# untitled.net
KiCad netlist of a schematic drawn in EAGLE
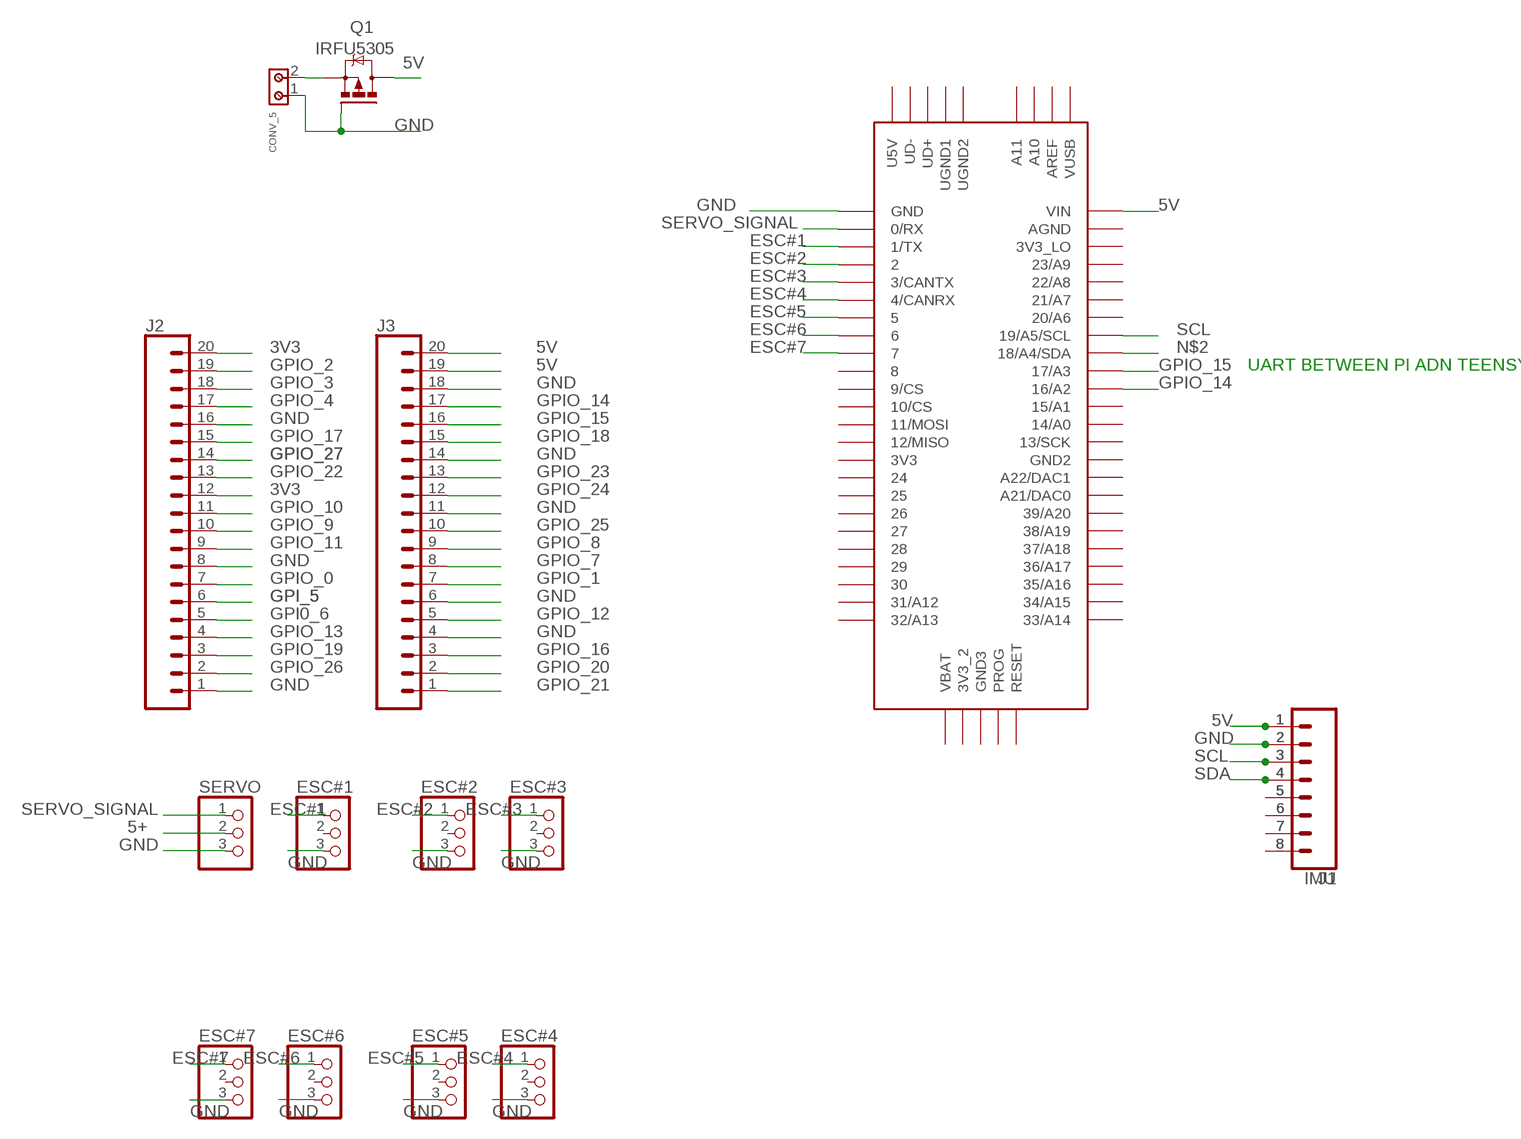
[diagram p0: schematic, sheet 1]

(export (version "E")
  (design (tool "Eeschema 10.0.6"))
  (components
    (comp (ref "CONV_5")
      (value "691213500002")
      (footprint "eagle-import:691213500002")
      (libsource (lib "eagle-import") (part "691213500002"))
    )
    (comp (ref "ESC#1")
      (value "PINHD-1X3")
      (footprint "eagle-import:1X03")
      (libsource (lib "eagle-import") (part "PINHD-1X3"))
    )
    (comp (ref "ESC#2")
      (value "PINHD-1X3")
      (footprint "eagle-import:1X03")
      (libsource (lib "eagle-import") (part "PINHD-1X3"))
    )
    (comp (ref "ESC#3")
      (value "PINHD-1X3")
      (footprint "eagle-import:1X03")
      (libsource (lib "eagle-import") (part "PINHD-1X3"))
    )
    (comp (ref "ESC#4")
      (value "PINHD-1X3")
      (footprint "eagle-import:1X03")
      (libsource (lib "eagle-import") (part "PINHD-1X3"))
    )
    (comp (ref "ESC#5")
      (value "PINHD-1X3")
      (footprint "eagle-import:1X03")
      (libsource (lib "eagle-import") (part "PINHD-1X3"))
    )
    (comp (ref "ESC#6")
      (value "PINHD-1X3")
      (footprint "eagle-import:1X03")
      (libsource (lib "eagle-import") (part "PINHD-1X3"))
    )
    (comp (ref "ESC#7")
      (value "PINHD-1X3")
      (footprint "eagle-import:1X03")
      (libsource (lib "eagle-import") (part "PINHD-1X3"))
    )
    (comp (ref "IMU")
      (value "CONN_08\"")
      (footprint "eagle-import:1X08")
      (libsource (lib "eagle-import") (part "CONN_08{dblquote}"))
    )
    (comp (ref "J1")
      (value "CONN_08\"")
      (footprint "eagle-import:1X08")
      (libsource (lib "eagle-import") (part "CONN_08{dblquote}"))
    )
    (comp (ref "J2")
      (value "CONN_20")
      (footprint "eagle-import:1X20")
      (libsource (lib "eagle-import") (part "CONN_20"))
    )
    (comp (ref "J3")
      (value "CONN_20")
      (footprint "eagle-import:1X20")
      (libsource (lib "eagle-import") (part "CONN_20"))
    )
    (comp (ref "Q1")
      (value "IRFU5305")
      (footprint "eagle-import:I-PAK_TO251AA")
      (libsource (lib "eagle-import") (part "IRF?5305U"))
    )
    (comp (ref "SERVO")
      (value "PINHD-1X3")
      (footprint "eagle-import:1X03")
      (libsource (lib "eagle-import") (part "PINHD-1X3"))
    )
    (comp (ref "U$1")
      (value "TEENSY_3.5/3.6")
      (footprint "eagle-import:TEENSY_3.5_3.6")
      (libsource (lib "eagle-import") (part "TEENSY_3.5/3.6"))
    )
  )
  (nets
    (net (code "1") (name "/3V3") (class "Default")
      (node (ref "J2") (pin "12") (pinfunction "12_12") (pintype "passive"))
      (node (ref "J2") (pin "20") (pinfunction "20_20") (pintype "passive"))
    )
    (net (code "2") (name "/5+") (class "Default")
      (node (ref "SERVO") (pin "2") (pinfunction "2_2") (pintype "passive"))
    )
    (net (code "3") (name "/5V") (class "Default")
      (node (ref "IMU") (pin "1") (pinfunction "1_1") (pintype "passive"))
      (node (ref "J1") (pin "1") (pinfunction "1_1") (pintype "passive"))
      (node (ref "J3") (pin "19") (pinfunction "19_19") (pintype "passive"))
      (node (ref "J3") (pin "20") (pinfunction "20_20") (pintype "passive"))
      (node (ref "Q1") (pin "2") (pinfunction "D_2") (pintype "passive"))
      (node (ref "U$1") (pin "VIN") (pinfunction "VIN_VIN") (pintype "bidirectional"))
    )
    (net (code "4") (name "/ESC#1") (class "Default")
      (node (ref "ESC#1") (pin "1") (pinfunction "1_1") (pintype "passive"))
      (node (ref "U$1") (pin "1/TX") (pinfunction "1/TX_1/TX") (pintype "bidirectional"))
    )
    (net (code "5") (name "/ESC#2") (class "Default")
      (node (ref "ESC#2") (pin "1") (pinfunction "1_1") (pintype "passive"))
      (node (ref "U$1") (pin "2") (pinfunction "2_2") (pintype "bidirectional"))
    )
    (net (code "6") (name "/ESC#3") (class "Default")
      (node (ref "ESC#3") (pin "1") (pinfunction "1_1") (pintype "passive"))
      (node (ref "U$1") (pin "3/CANTX") (pinfunction "3/CANTX_3/CANTX") (pintype "bidirectional"))
    )
    (net (code "7") (name "/ESC#4") (class "Default")
      (node (ref "ESC#4") (pin "1") (pinfunction "1_1") (pintype "passive"))
      (node (ref "U$1") (pin "4/CANRX") (pinfunction "4/CANRX_4/CANRX") (pintype "bidirectional"))
    )
    (net (code "8") (name "/ESC#5") (class "Default")
      (node (ref "ESC#5") (pin "1") (pinfunction "1_1") (pintype "passive"))
      (node (ref "U$1") (pin "5") (pinfunction "5_5") (pintype "bidirectional"))
    )
    (net (code "9") (name "/ESC#6") (class "Default")
      (node (ref "ESC#6") (pin "1") (pinfunction "1_1") (pintype "passive"))
      (node (ref "U$1") (pin "6") (pinfunction "6_6") (pintype "bidirectional"))
    )
    (net (code "10") (name "/ESC#7") (class "Default")
      (node (ref "ESC#7") (pin "1") (pinfunction "1_1") (pintype "passive"))
      (node (ref "U$1") (pin "7") (pinfunction "7_7") (pintype "bidirectional"))
    )
    (net (code "11") (name "/GND") (class "Default")
      (node (ref "CONV_5") (pin "1") (pinfunction "1_1") (pintype "passive"))
      (node (ref "ESC#1") (pin "3") (pinfunction "3_3") (pintype "passive"))
      (node (ref "ESC#2") (pin "3") (pinfunction "3_3") (pintype "passive"))
      (node (ref "ESC#3") (pin "3") (pinfunction "3_3") (pintype "passive"))
      (node (ref "ESC#4") (pin "3") (pinfunction "3_3") (pintype "passive"))
      (node (ref "ESC#5") (pin "3") (pinfunction "3_3") (pintype "passive"))
      (node (ref "ESC#6") (pin "3") (pinfunction "3_3") (pintype "passive"))
      (node (ref "ESC#7") (pin "3") (pinfunction "3_3") (pintype "passive"))
      (node (ref "IMU") (pin "2") (pinfunction "2_2") (pintype "passive"))
      (node (ref "J1") (pin "2") (pinfunction "2_2") (pintype "passive"))
      (node (ref "J2") (pin "1") (pinfunction "1_1") (pintype "passive"))
      (node (ref "J2") (pin "16") (pinfunction "16_16") (pintype "passive"))
      (node (ref "J2") (pin "8") (pinfunction "8_8") (pintype "passive"))
      (node (ref "J3") (pin "11") (pinfunction "11_11") (pintype "passive"))
      (node (ref "J3") (pin "14") (pinfunction "14_14") (pintype "passive"))
      (node (ref "J3") (pin "18") (pinfunction "18_18") (pintype "passive"))
      (node (ref "J3") (pin "4") (pinfunction "4_4") (pintype "passive"))
      (node (ref "J3") (pin "6") (pinfunction "6_6") (pintype "passive"))
      (node (ref "Q1") (pin "1") (pinfunction "G_1") (pintype "passive"))
      (node (ref "SERVO") (pin "3") (pinfunction "3_3") (pintype "passive"))
      (node (ref "U$1") (pin "GND") (pinfunction "GND_GND") (pintype "bidirectional"))
    )
    (net (code "12") (name "/GPI0_6") (class "Default")
      (node (ref "J2") (pin "5") (pinfunction "5_5") (pintype "passive"))
    )
    (net (code "13") (name "/GPIO_0") (class "Default")
      (node (ref "J2") (pin "7") (pinfunction "7_7") (pintype "passive"))
    )
    (net (code "14") (name "/GPIO_1") (class "Default")
      (node (ref "J3") (pin "7") (pinfunction "7_7") (pintype "passive"))
    )
    (net (code "15") (name "/GPIO_2") (class "Default")
      (node (ref "J2") (pin "19") (pinfunction "19_19") (pintype "passive"))
    )
    (net (code "16") (name "/GPIO_3") (class "Default")
      (node (ref "J2") (pin "18") (pinfunction "18_18") (pintype "passive"))
    )
    (net (code "17") (name "/GPIO_4") (class "Default")
      (node (ref "J2") (pin "17") (pinfunction "17_17") (pintype "passive"))
    )
    (net (code "18") (name "/GPIO_7") (class "Default")
      (node (ref "J3") (pin "8") (pinfunction "8_8") (pintype "passive"))
    )
    (net (code "19") (name "/GPIO_8") (class "Default")
      (node (ref "J3") (pin "9") (pinfunction "9_9") (pintype "passive"))
    )
    (net (code "20") (name "/GPIO_9") (class "Default")
      (node (ref "J2") (pin "10") (pinfunction "10_10") (pintype "passive"))
    )
    (net (code "21") (name "/GPIO_10") (class "Default")
      (node (ref "J2") (pin "11") (pinfunction "11_11") (pintype "passive"))
    )
    (net (code "22") (name "/GPIO_11") (class "Default")
      (node (ref "J2") (pin "9") (pinfunction "9_9") (pintype "passive"))
    )
    (net (code "23") (name "/GPIO_12") (class "Default")
      (node (ref "J3") (pin "5") (pinfunction "5_5") (pintype "passive"))
    )
    (net (code "24") (name "/GPIO_13") (class "Default")
      (node (ref "J2") (pin "4") (pinfunction "4_4") (pintype "passive"))
    )
    (net (code "25") (name "/GPIO_14") (class "Default")
      (node (ref "J3") (pin "17") (pinfunction "17_17") (pintype "passive"))
      (node (ref "U$1") (pin "16/A2") (pinfunction "16/A2_16/A2") (pintype "bidirectional"))
    )
    (net (code "26") (name "/GPIO_15") (class "Default")
      (node (ref "J3") (pin "16") (pinfunction "16_16") (pintype "passive"))
      (node (ref "U$1") (pin "17/A3") (pinfunction "17/A3_17/A3") (pintype "bidirectional"))
    )
    (net (code "27") (name "/GPIO_16") (class "Default")
      (node (ref "J3") (pin "3") (pinfunction "3_3") (pintype "passive"))
    )
    (net (code "28") (name "/GPIO_17") (class "Default")
      (node (ref "J2") (pin "15") (pinfunction "15_15") (pintype "passive"))
    )
    (net (code "29") (name "/GPIO_18") (class "Default")
      (node (ref "J3") (pin "15") (pinfunction "15_15") (pintype "passive"))
    )
    (net (code "30") (name "/GPIO_19") (class "Default")
      (node (ref "J2") (pin "3") (pinfunction "3_3") (pintype "passive"))
    )
    (net (code "31") (name "/GPIO_20") (class "Default")
      (node (ref "J3") (pin "2") (pinfunction "2_2") (pintype "passive"))
    )
    (net (code "32") (name "/GPIO_21") (class "Default")
      (node (ref "J3") (pin "1") (pinfunction "1_1") (pintype "passive"))
    )
    (net (code "33") (name "/GPIO_22") (class "Default")
      (node (ref "J2") (pin "13") (pinfunction "13_13") (pintype "passive"))
    )
    (net (code "34") (name "/GPIO_23") (class "Default")
      (node (ref "J3") (pin "13") (pinfunction "13_13") (pintype "passive"))
    )
    (net (code "35") (name "/GPIO_24") (class "Default")
      (node (ref "J3") (pin "12") (pinfunction "12_12") (pintype "passive"))
    )
    (net (code "36") (name "/GPIO_25") (class "Default")
      (node (ref "J3") (pin "10") (pinfunction "10_10") (pintype "passive"))
    )
    (net (code "37") (name "/GPIO_26") (class "Default")
      (node (ref "J2") (pin "2") (pinfunction "2_2") (pintype "passive"))
    )
    (net (code "38") (name "/GPIO_27") (class "Default")
      (node (ref "J2") (pin "14") (pinfunction "14_14") (pintype "passive"))
    )
    (net (code "39") (name "/GPI_5") (class "Default")
      (node (ref "J2") (pin "6") (pinfunction "6_6") (pintype "passive"))
    )
    (net (code "40") (name "/N$2") (class "Default")
      (node (ref "U$1") (pin "18/A4/SDA") (pinfunction "18/A4/SDA_18/A4/SDA") (pintype "bidirectional"))
    )
    (net (code "41") (name "/SCL") (class "Default")
      (node (ref "IMU") (pin "3") (pinfunction "3_3") (pintype "passive"))
      (node (ref "J1") (pin "3") (pinfunction "3_3") (pintype "passive"))
      (node (ref "U$1") (pin "19/A5/SCL") (pinfunction "19/A5/SCL_19/A5/SCL") (pintype "bidirectional"))
    )
    (net (code "42") (name "/SDA") (class "Default")
      (node (ref "IMU") (pin "4") (pinfunction "4_4") (pintype "passive"))
      (node (ref "J1") (pin "4") (pinfunction "4_4") (pintype "passive"))
    )
    (net (code "43") (name "/SERVO_SIGNAL") (class "Default")
      (node (ref "SERVO") (pin "1") (pinfunction "1_1") (pintype "passive"))
      (node (ref "U$1") (pin "0/RX") (pinfunction "0/RX_0/RX") (pintype "bidirectional"))
    )
    (net (code "44") (name "Net-(IMU-Pad5)") (class "Default")
      (node (ref "IMU") (pin "5") (pinfunction "5_5") (pintype "passive"))
      (node (ref "J1") (pin "5") (pinfunction "5_5") (pintype "passive"))
    )
    (net (code "45") (name "Net-(IMU-Pad6)") (class "Default")
      (node (ref "IMU") (pin "6") (pinfunction "6_6") (pintype "passive"))
      (node (ref "J1") (pin "6") (pinfunction "6_6") (pintype "passive"))
    )
    (net (code "46") (name "Net-(IMU-Pad7)") (class "Default")
      (node (ref "IMU") (pin "7") (pinfunction "7_7") (pintype "passive"))
      (node (ref "J1") (pin "7") (pinfunction "7_7") (pintype "passive"))
    )
    (net (code "47") (name "Net-(IMU-Pad8)") (class "Default")
      (node (ref "IMU") (pin "8") (pinfunction "8_8") (pintype "passive"))
      (node (ref "J1") (pin "8") (pinfunction "8_8") (pintype "passive"))
    )
    (net (code "48") (name "Net-(Q1-S)") (class "Default")
      (node (ref "CONV_5") (pin "2") (pinfunction "2_2") (pintype "passive"))
      (node (ref "Q1") (pin "3") (pinfunction "S_3") (pintype "passive"))
    )
    (net (code "49") (name "unconnected-(ESC#1-Pad2)") (class "Default")
      (node (ref "ESC#1") (pin "2") (pinfunction "2_2") (pintype "passive"))
    )
    (net (code "50") (name "unconnected-(ESC#2-Pad2)") (class "Default")
      (node (ref "ESC#2") (pin "2") (pinfunction "2_2") (pintype "passive"))
    )
    (net (code "51") (name "unconnected-(ESC#3-Pad2)") (class "Default")
      (node (ref "ESC#3") (pin "2") (pinfunction "2_2") (pintype "passive"))
    )
    (net (code "52") (name "unconnected-(ESC#4-Pad2)") (class "Default")
      (node (ref "ESC#4") (pin "2") (pinfunction "2_2") (pintype "passive"))
    )
    (net (code "53") (name "unconnected-(ESC#5-Pad2)") (class "Default")
      (node (ref "ESC#5") (pin "2") (pinfunction "2_2") (pintype "passive"))
    )
    (net (code "54") (name "unconnected-(ESC#6-Pad2)") (class "Default")
      (node (ref "ESC#6") (pin "2") (pinfunction "2_2") (pintype "passive"))
    )
    (net (code "55") (name "unconnected-(ESC#7-Pad2)") (class "Default")
      (node (ref "ESC#7") (pin "2") (pinfunction "2_2") (pintype "passive"))
    )
    (net (code "56") (name "unconnected-(U$1-A21{slash}DAC0-Pad21{slash}DAC0)") (class "Default")
      (node (ref "U$1") (pin "21/DAC0") (pinfunction "A21/DAC0_21/DAC0") (pintype "bidirectional"))
    )
    (net (code "57") (name "unconnected-(U$1-Pad3V3)") (class "Default")
      (node (ref "U$1") (pin "3V3") (pinfunction "3V3_3V3") (pintype "bidirectional"))
    )
    (net (code "58") (name "unconnected-(U$1-Pad3V3_2)") (class "Default")
      (node (ref "U$1") (pin "3V3_2") (pinfunction "3V3_2_3V3_2") (pintype "bidirectional"))
    )
    (net (code "59") (name "unconnected-(U$1-Pad3V3_LO)") (class "Default")
      (node (ref "U$1") (pin "3V3_LO") (pinfunction "3V3_LO_3V3_LO") (pintype "bidirectional"))
    )
    (net (code "60") (name "unconnected-(U$1-Pad8)") (class "Default")
      (node (ref "U$1") (pin "8") (pinfunction "8_8") (pintype "bidirectional"))
    )
    (net (code "61") (name "unconnected-(U$1-Pad9{slash}CS)") (class "Default")
      (node (ref "U$1") (pin "9/CS") (pinfunction "9/CS_9/CS") (pintype "bidirectional"))
    )
    (net (code "62") (name "unconnected-(U$1-Pad10{slash}CS)") (class "Default")
      (node (ref "U$1") (pin "10/CS") (pinfunction "10/CS_10/CS") (pintype "bidirectional"))
    )
    (net (code "63") (name "unconnected-(U$1-Pad11{slash}MOSI)") (class "Default")
      (node (ref "U$1") (pin "11/MOSI") (pinfunction "11/MOSI_11/MOSI") (pintype "bidirectional"))
    )
    (net (code "64") (name "unconnected-(U$1-Pad12{slash}MISO)") (class "Default")
      (node (ref "U$1") (pin "12/MISO") (pinfunction "12/MISO_12/MISO") (pintype "bidirectional"))
    )
    (net (code "65") (name "unconnected-(U$1-Pad13{slash}SCK)") (class "Default")
      (node (ref "U$1") (pin "13/SCK") (pinfunction "13/SCK_13/SCK") (pintype "bidirectional"))
    )
    (net (code "66") (name "unconnected-(U$1-Pad14{slash}A0)") (class "Default")
      (node (ref "U$1") (pin "14/A0") (pinfunction "14/A0_14/A0") (pintype "bidirectional"))
    )
    (net (code "67") (name "unconnected-(U$1-Pad15{slash}A1)") (class "Default")
      (node (ref "U$1") (pin "15/A1") (pinfunction "15/A1_15/A1") (pintype "bidirectional"))
    )
    (net (code "68") (name "unconnected-(U$1-Pad20{slash}A6)") (class "Default")
      (node (ref "U$1") (pin "20/A6") (pinfunction "20/A6_20/A6") (pintype "bidirectional"))
    )
    (net (code "69") (name "unconnected-(U$1-Pad21{slash}A7)") (class "Default")
      (node (ref "U$1") (pin "21/A7") (pinfunction "21/A7_21/A7") (pintype "bidirectional"))
    )
    (net (code "70") (name "unconnected-(U$1-Pad22{slash}A8)") (class "Default")
      (node (ref "U$1") (pin "22/A8") (pinfunction "22/A8_22/A8") (pintype "bidirectional"))
    )
    (net (code "71") (name "unconnected-(U$1-Pad23{slash}A9)") (class "Default")
      (node (ref "U$1") (pin "23/A9") (pinfunction "23/A9_23/A9") (pintype "bidirectional"))
    )
    (net (code "72") (name "unconnected-(U$1-Pad24)") (class "Default")
      (node (ref "U$1") (pin "24") (pinfunction "24_24") (pintype "bidirectional"))
    )
    (net (code "73") (name "unconnected-(U$1-Pad25)") (class "Default")
      (node (ref "U$1") (pin "25") (pinfunction "25_25") (pintype "bidirectional"))
    )
    (net (code "74") (name "unconnected-(U$1-Pad26)") (class "Default")
      (node (ref "U$1") (pin "26") (pinfunction "26_26") (pintype "bidirectional"))
    )
    (net (code "75") (name "unconnected-(U$1-Pad27)") (class "Default")
      (node (ref "U$1") (pin "27") (pinfunction "27_27") (pintype "bidirectional"))
    )
    (net (code "76") (name "unconnected-(U$1-Pad28)") (class "Default")
      (node (ref "U$1") (pin "28") (pinfunction "28_28") (pintype "bidirectional"))
    )
    (net (code "77") (name "unconnected-(U$1-Pad29)") (class "Default")
      (node (ref "U$1") (pin "29") (pinfunction "29_29") (pintype "bidirectional"))
    )
    (net (code "78") (name "unconnected-(U$1-Pad30)") (class "Default")
      (node (ref "U$1") (pin "30") (pinfunction "30_30") (pintype "bidirectional"))
    )
    (net (code "79") (name "unconnected-(U$1-Pad31{slash}A12)") (class "Default")
      (node (ref "U$1") (pin "31/A12") (pinfunction "31/A12_31/A12") (pintype "bidirectional"))
    )
    (net (code "80") (name "unconnected-(U$1-Pad32{slash}A13)") (class "Default")
      (node (ref "U$1") (pin "32/A13") (pinfunction "32/A13_32/A13") (pintype "bidirectional"))
    )
    (net (code "81") (name "unconnected-(U$1-Pad33{slash}A14)") (class "Default")
      (node (ref "U$1") (pin "33/A14") (pinfunction "33/A14_33/A14") (pintype "bidirectional"))
    )
    (net (code "82") (name "unconnected-(U$1-Pad34{slash}A15)") (class "Default")
      (node (ref "U$1") (pin "34/A15") (pinfunction "34/A15_34/A15") (pintype "bidirectional"))
    )
    (net (code "83") (name "unconnected-(U$1-Pad35{slash}A16)") (class "Default")
      (node (ref "U$1") (pin "35/A16") (pinfunction "35/A16_35/A16") (pintype "bidirectional"))
    )
    (net (code "84") (name "unconnected-(U$1-Pad36{slash}A17)") (class "Default")
      (node (ref "U$1") (pin "36/A17") (pinfunction "36/A17_36/A17") (pintype "bidirectional"))
    )
    (net (code "85") (name "unconnected-(U$1-Pad37{slash}A18)") (class "Default")
      (node (ref "U$1") (pin "37/A18") (pinfunction "37/A18_37/A18") (pintype "bidirectional"))
    )
    (net (code "86") (name "unconnected-(U$1-Pad38{slash}A19)") (class "Default")
      (node (ref "U$1") (pin "38/A19") (pinfunction "38/A19_38/A19") (pintype "bidirectional"))
    )
    (net (code "87") (name "unconnected-(U$1-Pad39{slash}A20)") (class "Default")
      (node (ref "U$1") (pin "39/A20") (pinfunction "39/A20_39/A20") (pintype "bidirectional"))
    )
    (net (code "88") (name "unconnected-(U$1-PadA10)") (class "Default")
      (node (ref "U$1") (pin "A10") (pinfunction "A10_A10") (pintype "bidirectional"))
    )
    (net (code "89") (name "unconnected-(U$1-PadA11)") (class "Default")
      (node (ref "U$1") (pin "A11") (pinfunction "A11_A11") (pintype "bidirectional"))
    )
    (net (code "90") (name "unconnected-(U$1-PadA22{slash}DAC1)") (class "Default")
      (node (ref "U$1") (pin "A22/DAC1") (pinfunction "A22/DAC1_A22/DAC1") (pintype "bidirectional"))
    )
    (net (code "91") (name "unconnected-(U$1-PadAGND)") (class "Default")
      (node (ref "U$1") (pin "AGND") (pinfunction "AGND_AGND") (pintype "bidirectional"))
    )
    (net (code "92") (name "unconnected-(U$1-PadAREF)") (class "Default")
      (node (ref "U$1") (pin "AREF") (pinfunction "AREF_AREF") (pintype "bidirectional"))
    )
    (net (code "93") (name "unconnected-(U$1-PadGND2)") (class "Default")
      (node (ref "U$1") (pin "GND2") (pinfunction "GND2_GND2") (pintype "bidirectional"))
    )
    (net (code "94") (name "unconnected-(U$1-PadGND3)") (class "Default")
      (node (ref "U$1") (pin "GND3") (pinfunction "GND3_GND3") (pintype "bidirectional"))
    )
    (net (code "95") (name "unconnected-(U$1-PadPROG)") (class "Default")
      (node (ref "U$1") (pin "PROG") (pinfunction "PROG_PROG") (pintype "bidirectional"))
    )
    (net (code "96") (name "unconnected-(U$1-PadRESET)") (class "Default")
      (node (ref "U$1") (pin "RESET") (pinfunction "RESET_RESET") (pintype "bidirectional"))
    )
    (net (code "97") (name "unconnected-(U$1-PadU5V)") (class "Default")
      (node (ref "U$1") (pin "U5V") (pinfunction "U5V_U5V") (pintype "bidirectional"))
    )
    (net (code "98") (name "unconnected-(U$1-PadUD+)") (class "Default")
      (node (ref "U$1") (pin "UD+") (pinfunction "UD+_UD+") (pintype "bidirectional"))
    )
    (net (code "99") (name "unconnected-(U$1-PadUD-)") (class "Default")
      (node (ref "U$1") (pin "UD-") (pinfunction "UD-_UD-") (pintype "bidirectional"))
    )
    (net (code "100") (name "unconnected-(U$1-PadUGND1)") (class "Default")
      (node (ref "U$1") (pin "UGND1") (pinfunction "UGND1_UGND1") (pintype "bidirectional"))
    )
    (net (code "101") (name "unconnected-(U$1-PadUGND2)") (class "Default")
      (node (ref "U$1") (pin "UGND2") (pinfunction "UGND2_UGND2") (pintype "bidirectional"))
    )
    (net (code "102") (name "unconnected-(U$1-PadVBAT)") (class "Default")
      (node (ref "U$1") (pin "VBAT") (pinfunction "VBAT_VBAT") (pintype "bidirectional"))
    )
    (net (code "103") (name "unconnected-(U$1-PadVUSB)") (class "Default")
      (node (ref "U$1") (pin "VUSB") (pinfunction "VUSB_VUSB") (pintype "bidirectional"))
    )
  )
)
